# ESCON_Module_48.net
KiCad netlist of a schematic drawn in EAGLE
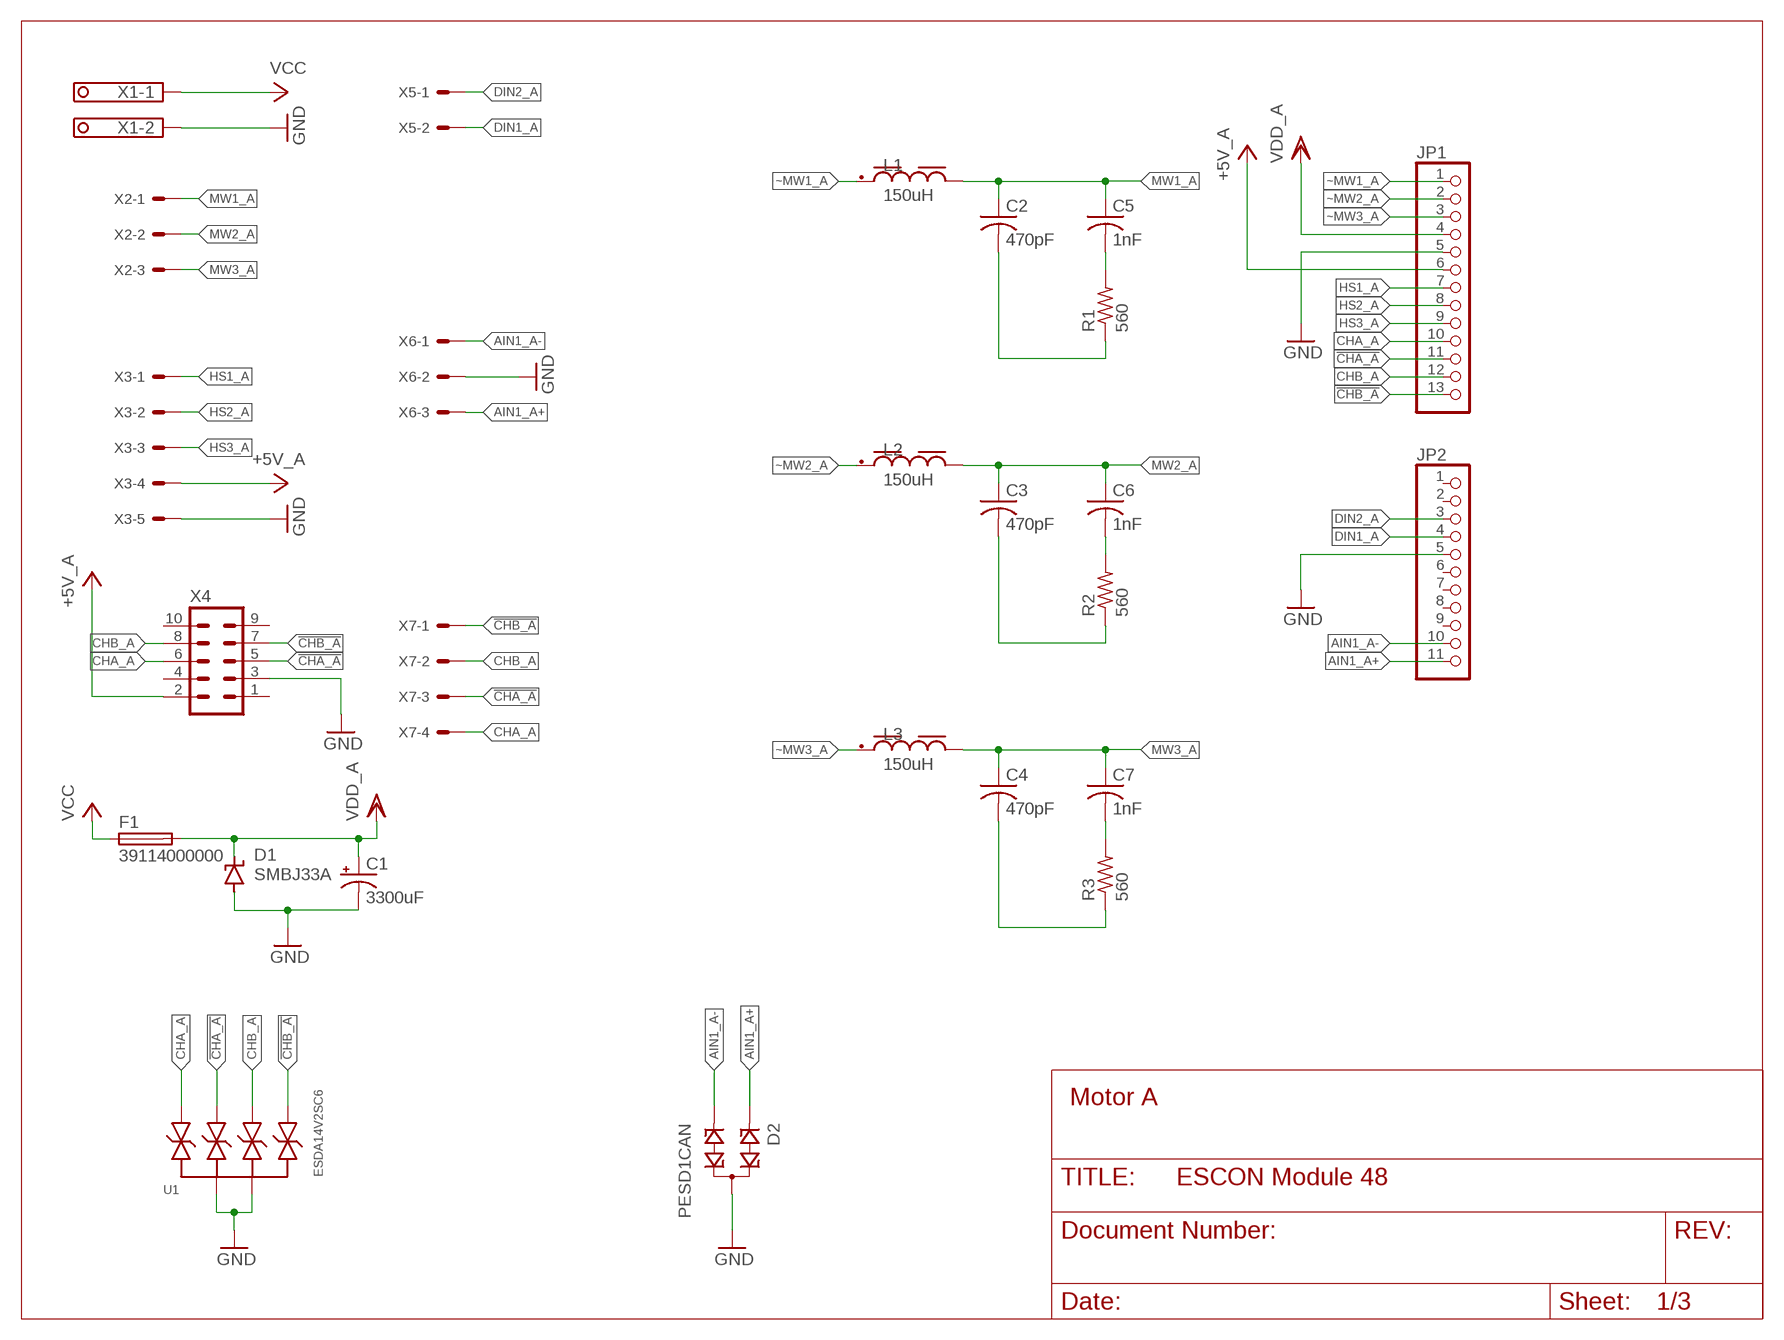
[diagram p0: schematic, sheet 1]
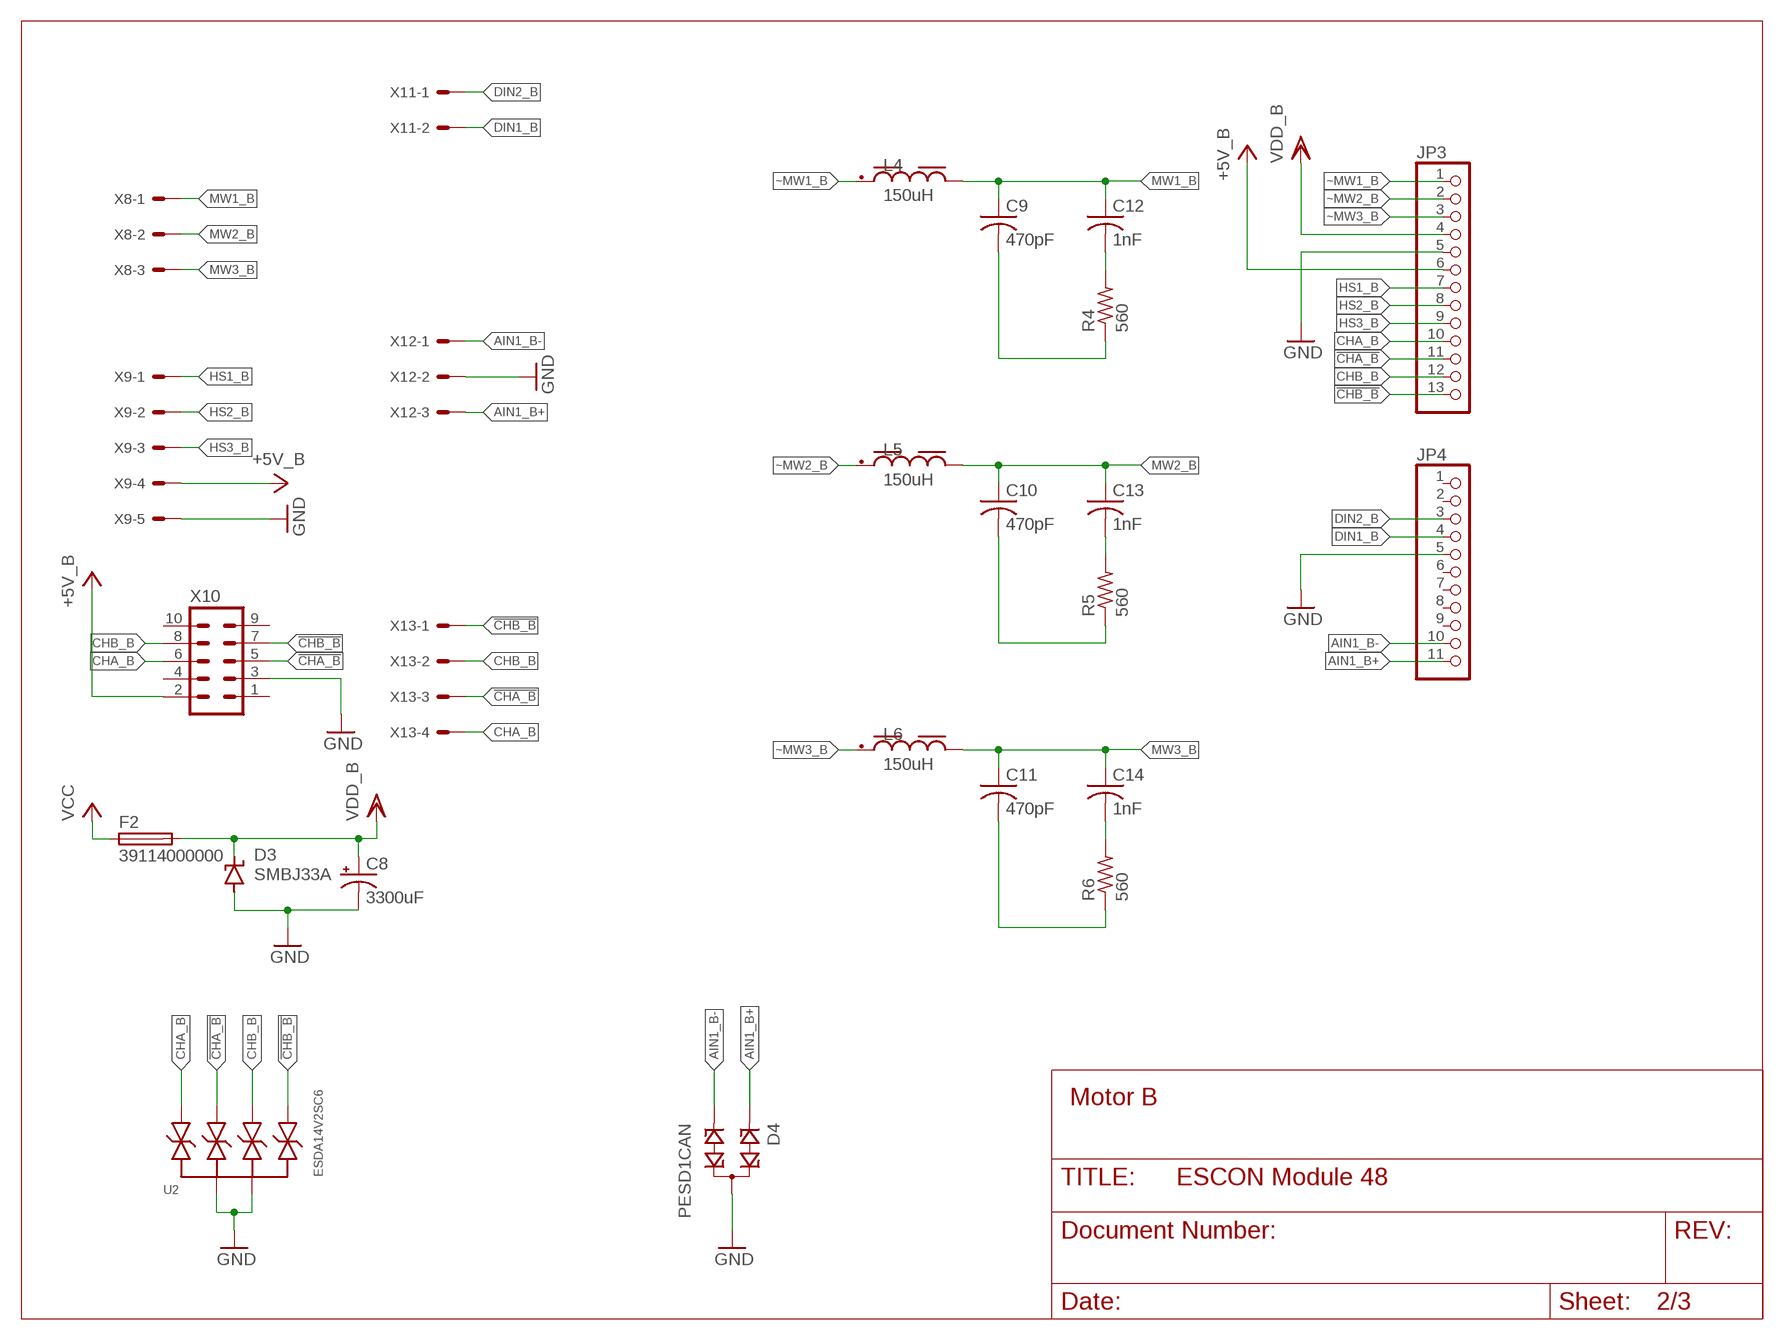
[diagram p1: schematic, sheet 2]
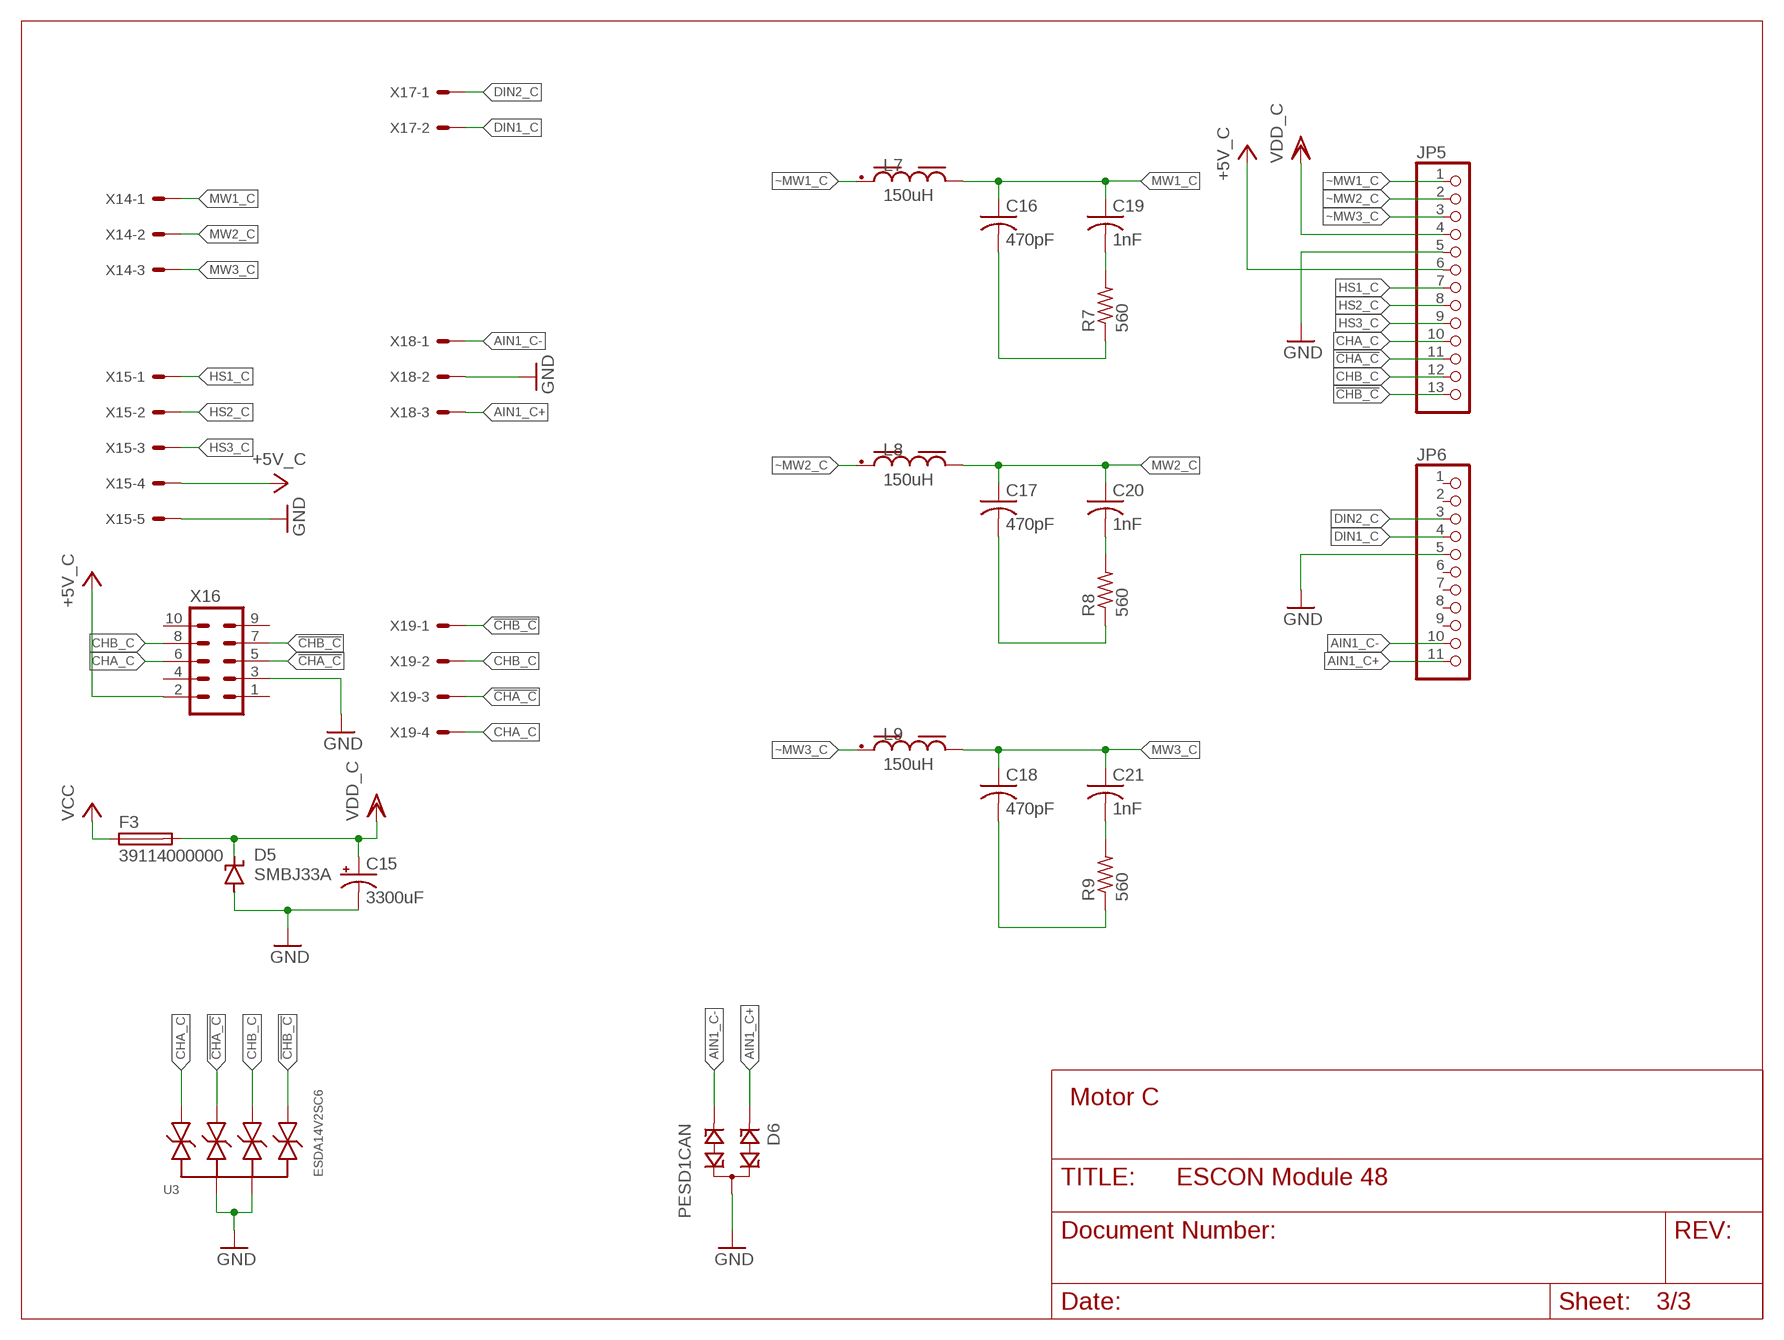
[diagram p2: schematic, sheet 3]

(export (version "E")
  (design (tool "Eeschema 10.0.6"))
  (components
    (comp (ref "C8")
      (value "3300uF")
      (footprint "eagle-import:E7,5-18")
      (libsource (lib "eagle-import") (part "CPOL-USE7.5-18"))
    )
    (comp (ref "C9")
      (value "470pF")
      (footprint "eagle-import:C0603")
      (libsource (lib "eagle-import") (part "C-USC0603"))
    )
    (comp (ref "C10")
      (value "470pF")
      (footprint "eagle-import:C0603")
      (libsource (lib "eagle-import") (part "C-USC0603"))
    )
    (comp (ref "C11")
      (value "470pF")
      (footprint "eagle-import:C0603")
      (libsource (lib "eagle-import") (part "C-USC0603"))
    )
    (comp (ref "C12")
      (value "1nF")
      (footprint "eagle-import:C0603")
      (libsource (lib "eagle-import") (part "C-USC0603"))
    )
    (comp (ref "C13")
      (value "1nF")
      (footprint "eagle-import:C0603")
      (libsource (lib "eagle-import") (part "C-USC0603"))
    )
    (comp (ref "C14")
      (value "1nF")
      (footprint "eagle-import:C0603")
      (libsource (lib "eagle-import") (part "C-USC0603"))
    )
    (comp (ref "D3")
      (value "SMBJ33A")
      (footprint "eagle-import:SMBJ")
      (libsource (lib "eagle-import") (part "SUPPRESSOR-SMBJ"))
    )
    (comp (ref "D4")
      (value "PESD1CAN")
      (footprint "eagle-import:SOT23")
      (libsource (lib "eagle-import") (part "PESD1CAN"))
    )
    (comp (ref "F2")
      (value "39114000000")
      (footprint "eagle-import:TE5")
      (libsource (lib "eagle-import") (part "TE5"))
    )
    (comp (ref "JP3")
      (value "PINHD-1X13")
      (footprint "eagle-import:1X13")
      (libsource (lib "eagle-import") (part "PINHD-1X13"))
    )
    (comp (ref "JP4")
      (value "PINHD-1X11")
      (footprint "eagle-import:1X11")
      (libsource (lib "eagle-import") (part "PINHD-1X11"))
    )
    (comp (ref "L4")
      (value "150uH")
      (footprint "eagle-import:WE-PD_1210")
      (libsource (lib "eagle-import") (part "WE-PD_1210_7447709151"))
    )
    (comp (ref "L5")
      (value "150uH")
      (footprint "eagle-import:WE-PD_1210")
      (libsource (lib "eagle-import") (part "WE-PD_1210_7447709151"))
    )
    (comp (ref "L6")
      (value "150uH")
      (footprint "eagle-import:WE-PD_1210")
      (libsource (lib "eagle-import") (part "WE-PD_1210_7447709151"))
    )
    (comp (ref "R4")
      (value "560")
      (footprint "eagle-import:R0603")
      (libsource (lib "eagle-import") (part "R-US_R0603"))
    )
    (comp (ref "R5")
      (value "560")
      (footprint "eagle-import:R0603")
      (libsource (lib "eagle-import") (part "R-US_R0603"))
    )
    (comp (ref "R6")
      (value "560")
      (footprint "eagle-import:R0603")
      (libsource (lib "eagle-import") (part "R-US_R0603"))
    )
    (comp (ref "U2")
      (value "ESDA14V2SC6")
      (footprint "eagle-import:SOT95P280X145-6N")
      (fields (field (name "MF") "STMicroelectronics"))
      (libsource (lib "eagle-import") (part "ESDA14V2SC6"))
    )
    (comp (ref "X8")
      (value "JST-XH-03-PIN-LONG-PAD")
      (footprint "eagle-import:JST-XH-03-PACKAGE-LONG-PAD")
      (libsource (lib "eagle-import") (part "JST-XH-03-PIN-LONG-PAD"))
    )
    (comp (ref "X9")
      (value "JST-XH-05-PIN-LONG-PAD")
      (footprint "eagle-import:JST-XH-05-PACKAGE-LONG-PAD")
      (libsource (lib "eagle-import") (part "JST-XH-05-PIN-LONG-PAD"))
    )
    (comp (ref "X10")
      (value "ML10LP-V")
      (footprint "eagle-import:10LP-V")
      (libsource (lib "eagle-import") (part "ML10LP-V"))
    )
    (comp (ref "X11")
      (value "JST-XH-02-PIN-LONG-PAD")
      (footprint "eagle-import:JST-XH-02-PACKAGE-LONG-PAD")
      (libsource (lib "eagle-import") (part "JST-XH-02-PIN-LONG-PAD"))
    )
    (comp (ref "X12")
      (value "JST-XH-03-PIN-LONG-PAD")
      (footprint "eagle-import:JST-XH-03-PACKAGE-LONG-PAD")
      (libsource (lib "eagle-import") (part "JST-XH-03-PIN-LONG-PAD"))
    )
    (comp (ref "X13")
      (value "JST-XH-04-PIN-LONG-PAD")
      (footprint "eagle-import:JST-XH-04-PACKAGE-LONG-PAD")
      (libsource (lib "eagle-import") (part "JST-XH-04-PIN-LONG-PAD"))
    )
    (comp (ref "C15")
      (value "3300uF")
      (footprint "eagle-import:E7,5-18")
      (libsource (lib "eagle-import") (part "CPOL-USE7.5-18"))
    )
    (comp (ref "C16")
      (value "470pF")
      (footprint "eagle-import:C0603")
      (libsource (lib "eagle-import") (part "C-USC0603"))
    )
    (comp (ref "C17")
      (value "470pF")
      (footprint "eagle-import:C0603")
      (libsource (lib "eagle-import") (part "C-USC0603"))
    )
    (comp (ref "C18")
      (value "470pF")
      (footprint "eagle-import:C0603")
      (libsource (lib "eagle-import") (part "C-USC0603"))
    )
    (comp (ref "C19")
      (value "1nF")
      (footprint "eagle-import:C0603")
      (libsource (lib "eagle-import") (part "C-USC0603"))
    )
    (comp (ref "C20")
      (value "1nF")
      (footprint "eagle-import:C0603")
      (libsource (lib "eagle-import") (part "C-USC0603"))
    )
    (comp (ref "C21")
      (value "1nF")
      (footprint "eagle-import:C0603")
      (libsource (lib "eagle-import") (part "C-USC0603"))
    )
    (comp (ref "D5")
      (value "SMBJ33A")
      (footprint "eagle-import:SMBJ")
      (libsource (lib "eagle-import") (part "SUPPRESSOR-SMBJ"))
    )
    (comp (ref "D6")
      (value "PESD1CAN")
      (footprint "eagle-import:SOT23")
      (libsource (lib "eagle-import") (part "PESD1CAN"))
    )
    (comp (ref "F3")
      (value "39114000000")
      (footprint "eagle-import:TE5")
      (libsource (lib "eagle-import") (part "TE5"))
    )
    (comp (ref "JP5")
      (value "PINHD-1X13")
      (footprint "eagle-import:1X13")
      (libsource (lib "eagle-import") (part "PINHD-1X13"))
    )
    (comp (ref "JP6")
      (value "PINHD-1X11")
      (footprint "eagle-import:1X11")
      (libsource (lib "eagle-import") (part "PINHD-1X11"))
    )
    (comp (ref "L7")
      (value "150uH")
      (footprint "eagle-import:WE-PD_1210")
      (libsource (lib "eagle-import") (part "WE-PD_1210_7447709151"))
    )
    (comp (ref "L8")
      (value "150uH")
      (footprint "eagle-import:WE-PD_1210")
      (libsource (lib "eagle-import") (part "WE-PD_1210_7447709151"))
    )
    (comp (ref "L9")
      (value "150uH")
      (footprint "eagle-import:WE-PD_1210")
      (libsource (lib "eagle-import") (part "WE-PD_1210_7447709151"))
    )
    (comp (ref "R7")
      (value "560")
      (footprint "eagle-import:R0603")
      (libsource (lib "eagle-import") (part "R-US_R0603"))
    )
    (comp (ref "R8")
      (value "560")
      (footprint "eagle-import:R0603")
      (libsource (lib "eagle-import") (part "R-US_R0603"))
    )
    (comp (ref "R9")
      (value "560")
      (footprint "eagle-import:R0603")
      (libsource (lib "eagle-import") (part "R-US_R0603"))
    )
    (comp (ref "U3")
      (value "ESDA14V2SC6")
      (footprint "eagle-import:SOT95P280X145-6N")
      (fields (field (name "MF") "STMicroelectronics"))
      (libsource (lib "eagle-import") (part "ESDA14V2SC6"))
    )
    (comp (ref "X14")
      (value "JST-XH-03-PIN-LONG-PAD")
      (footprint "eagle-import:JST-XH-03-PACKAGE-LONG-PAD")
      (libsource (lib "eagle-import") (part "JST-XH-03-PIN-LONG-PAD"))
    )
    (comp (ref "X15")
      (value "JST-XH-05-PIN-LONG-PAD")
      (footprint "eagle-import:JST-XH-05-PACKAGE-LONG-PAD")
      (libsource (lib "eagle-import") (part "JST-XH-05-PIN-LONG-PAD"))
    )
    (comp (ref "X16")
      (value "ML10LP-V")
      (footprint "eagle-import:10LP-V")
      (libsource (lib "eagle-import") (part "ML10LP-V"))
    )
    (comp (ref "X17")
      (value "JST-XH-02-PIN-LONG-PAD")
      (footprint "eagle-import:JST-XH-02-PACKAGE-LONG-PAD")
      (libsource (lib "eagle-import") (part "JST-XH-02-PIN-LONG-PAD"))
    )
    (comp (ref "X18")
      (value "JST-XH-03-PIN-LONG-PAD")
      (footprint "eagle-import:JST-XH-03-PACKAGE-LONG-PAD")
      (libsource (lib "eagle-import") (part "JST-XH-03-PIN-LONG-PAD"))
    )
    (comp (ref "X19")
      (value "JST-XH-04-PIN-LONG-PAD")
      (footprint "eagle-import:JST-XH-04-PACKAGE-LONG-PAD")
      (libsource (lib "eagle-import") (part "JST-XH-04-PIN-LONG-PAD"))
    )
    (comp (ref "C1")
      (value "3300uF")
      (footprint "eagle-import:E7,5-18")
      (libsource (lib "eagle-import") (part "CPOL-USE7.5-18"))
    )
    (comp (ref "C2")
      (value "470pF")
      (footprint "eagle-import:C0603")
      (libsource (lib "eagle-import") (part "C-USC0603"))
    )
    (comp (ref "C3")
      (value "470pF")
      (footprint "eagle-import:C0603")
      (libsource (lib "eagle-import") (part "C-USC0603"))
    )
    (comp (ref "C4")
      (value "470pF")
      (footprint "eagle-import:C0603")
      (libsource (lib "eagle-import") (part "C-USC0603"))
    )
    (comp (ref "C5")
      (value "1nF")
      (footprint "eagle-import:C0603")
      (libsource (lib "eagle-import") (part "C-USC0603"))
    )
    (comp (ref "C6")
      (value "1nF")
      (footprint "eagle-import:C0603")
      (libsource (lib "eagle-import") (part "C-USC0603"))
    )
    (comp (ref "C7")
      (value "1nF")
      (footprint "eagle-import:C0603")
      (libsource (lib "eagle-import") (part "C-USC0603"))
    )
    (comp (ref "D1")
      (value "SMBJ33A")
      (footprint "eagle-import:SMBJ")
      (libsource (lib "eagle-import") (part "SUPPRESSOR-SMBJ"))
    )
    (comp (ref "D2")
      (value "PESD1CAN")
      (footprint "eagle-import:SOT23")
      (libsource (lib "eagle-import") (part "PESD1CAN"))
    )
    (comp (ref "F1")
      (value "39114000000")
      (footprint "eagle-import:TE5")
      (libsource (lib "eagle-import") (part "TE5"))
    )
    (comp (ref "JP1")
      (value "PINHD-1X13")
      (footprint "eagle-import:1X13")
      (libsource (lib "eagle-import") (part "PINHD-1X13"))
    )
    (comp (ref "JP2")
      (value "PINHD-1X11")
      (footprint "eagle-import:1X11")
      (libsource (lib "eagle-import") (part "PINHD-1X11"))
    )
    (comp (ref "L1")
      (value "150uH")
      (footprint "eagle-import:WE-PD_1210")
      (libsource (lib "eagle-import") (part "WE-PD_1210_7447709151"))
    )
    (comp (ref "L2")
      (value "150uH")
      (footprint "eagle-import:WE-PD_1210")
      (libsource (lib "eagle-import") (part "WE-PD_1210_7447709151"))
    )
    (comp (ref "L3")
      (value "150uH")
      (footprint "eagle-import:WE-PD_1210")
      (libsource (lib "eagle-import") (part "WE-PD_1210_7447709151"))
    )
    (comp (ref "R1")
      (value "560")
      (footprint "eagle-import:R0603")
      (libsource (lib "eagle-import") (part "R-US_R0603"))
    )
    (comp (ref "R2")
      (value "560")
      (footprint "eagle-import:R0603")
      (libsource (lib "eagle-import") (part "R-US_R0603"))
    )
    (comp (ref "R3")
      (value "560")
      (footprint "eagle-import:R0603")
      (libsource (lib "eagle-import") (part "R-US_R0603"))
    )
    (comp (ref "U1")
      (value "ESDA14V2SC6")
      (footprint "eagle-import:SOT95P280X145-6N")
      (fields (field (name "MF") "STMicroelectronics"))
      (libsource (lib "eagle-import") (part "ESDA14V2SC6"))
    )
    (comp (ref "X1")
      (value "TERMINAL-BLOCK-3.5MM-2-PIN-LONG-PAD")
      (footprint "eagle-import:TERMINAL-BLOCK-2-PIN-3.5MM-LONG-PAD")
      (libsource (lib "eagle-import") (part "TERMINAL-BLOCK-3.5MM-2-PIN-LONG-PAD"))
    )
    (comp (ref "X2")
      (value "JST-XH-03-PIN-LONG-PAD")
      (footprint "eagle-import:JST-XH-03-PACKAGE-LONG-PAD")
      (libsource (lib "eagle-import") (part "JST-XH-03-PIN-LONG-PAD"))
    )
    (comp (ref "X3")
      (value "JST-XH-05-PIN-LONG-PAD")
      (footprint "eagle-import:JST-XH-05-PACKAGE-LONG-PAD")
      (libsource (lib "eagle-import") (part "JST-XH-05-PIN-LONG-PAD"))
    )
    (comp (ref "X4")
      (value "ML10LP-V")
      (footprint "eagle-import:10LP-V")
      (libsource (lib "eagle-import") (part "ML10LP-V"))
    )
    (comp (ref "X5")
      (value "JST-XH-02-PIN-LONG-PAD")
      (footprint "eagle-import:JST-XH-02-PACKAGE-LONG-PAD")
      (libsource (lib "eagle-import") (part "JST-XH-02-PIN-LONG-PAD"))
    )
    (comp (ref "X6")
      (value "JST-XH-03-PIN-LONG-PAD")
      (footprint "eagle-import:JST-XH-03-PACKAGE-LONG-PAD")
      (libsource (lib "eagle-import") (part "JST-XH-03-PIN-LONG-PAD"))
    )
    (comp (ref "X7")
      (value "JST-XH-04-PIN-LONG-PAD")
      (footprint "eagle-import:JST-XH-04-PACKAGE-LONG-PAD")
      (libsource (lib "eagle-import") (part "JST-XH-04-PIN-LONG-PAD"))
    )
  )
  (nets
    (net (code "1") (name "+5V_A") (class "Default")
      (node (ref "JP1") (pin "6") (pinfunction "6_6") (pintype "passive"))
      (node (ref "X3") (pin "4") (pinfunction "S_4") (pintype "passive"))
      (node (ref "X4") (pin "2") (pinfunction "2_2") (pintype "bidirectional"))
    )
    (net (code "2") (name "+5V_B") (class "Default")
      (node (ref "JP3") (pin "6") (pinfunction "6_6") (pintype "passive"))
      (node (ref "X10") (pin "2") (pinfunction "2_2") (pintype "bidirectional"))
      (node (ref "X9") (pin "4") (pinfunction "S_4") (pintype "passive"))
    )
    (net (code "3") (name "+5V_C") (class "Default")
      (node (ref "JP5") (pin "6") (pinfunction "6_6") (pintype "passive"))
      (node (ref "X15") (pin "4") (pinfunction "S_4") (pintype "passive"))
      (node (ref "X16") (pin "2") (pinfunction "2_2") (pintype "bidirectional"))
    )
    (net (code "4") (name "AIN1_A+") (class "Default")
      (node (ref "D2") (pin "1") (pinfunction "1_1") (pintype "passive"))
      (node (ref "JP2") (pin "11") (pinfunction "11_11") (pintype "passive"))
      (node (ref "X6") (pin "3") (pinfunction "S_3") (pintype "passive"))
    )
    (net (code "5") (name "AIN1_A-") (class "Default")
      (node (ref "D2") (pin "2") (pinfunction "2_2") (pintype "passive"))
      (node (ref "JP2") (pin "10") (pinfunction "10_10") (pintype "passive"))
      (node (ref "X6") (pin "1") (pinfunction "S_1") (pintype "passive"))
    )
    (net (code "6") (name "AIN1_B+") (class "Default")
      (node (ref "D4") (pin "1") (pinfunction "1_1") (pintype "passive"))
      (node (ref "JP4") (pin "11") (pinfunction "11_11") (pintype "passive"))
      (node (ref "X12") (pin "3") (pinfunction "S_3") (pintype "passive"))
    )
    (net (code "7") (name "AIN1_B-") (class "Default")
      (node (ref "D4") (pin "2") (pinfunction "2_2") (pintype "passive"))
      (node (ref "JP4") (pin "10") (pinfunction "10_10") (pintype "passive"))
      (node (ref "X12") (pin "1") (pinfunction "S_1") (pintype "passive"))
    )
    (net (code "8") (name "AIN1_C+") (class "Default")
      (node (ref "D6") (pin "1") (pinfunction "1_1") (pintype "passive"))
      (node (ref "JP6") (pin "11") (pinfunction "11_11") (pintype "passive"))
      (node (ref "X18") (pin "3") (pinfunction "S_3") (pintype "passive"))
    )
    (net (code "9") (name "AIN1_C-") (class "Default")
      (node (ref "D6") (pin "2") (pinfunction "2_2") (pintype "passive"))
      (node (ref "JP6") (pin "10") (pinfunction "10_10") (pintype "passive"))
      (node (ref "X18") (pin "1") (pinfunction "S_1") (pintype "passive"))
    )
    (net (code "10") (name "CHA_A") (class "Default")
      (node (ref "JP1") (pin "10") (pinfunction "10_10") (pintype "passive"))
      (node (ref "U1") (pin "1") (pinfunction "1_1") (pintype "passive"))
      (node (ref "X4") (pin "6") (pinfunction "6_6") (pintype "bidirectional"))
      (node (ref "X7") (pin "4") (pinfunction "S_4") (pintype "passive"))
    )
    (net (code "11") (name "CHA_B") (class "Default")
      (node (ref "JP3") (pin "10") (pinfunction "10_10") (pintype "passive"))
      (node (ref "U2") (pin "1") (pinfunction "1_1") (pintype "passive"))
      (node (ref "X10") (pin "6") (pinfunction "6_6") (pintype "bidirectional"))
      (node (ref "X13") (pin "4") (pinfunction "S_4") (pintype "passive"))
    )
    (net (code "12") (name "CHA_C") (class "Default")
      (node (ref "JP5") (pin "10") (pinfunction "10_10") (pintype "passive"))
      (node (ref "U3") (pin "1") (pinfunction "1_1") (pintype "passive"))
      (node (ref "X16") (pin "6") (pinfunction "6_6") (pintype "bidirectional"))
      (node (ref "X19") (pin "4") (pinfunction "S_4") (pintype "passive"))
    )
    (net (code "13") (name "CHB_A") (class "Default")
      (node (ref "JP1") (pin "12") (pinfunction "12_12") (pintype "passive"))
      (node (ref "U1") (pin "4") (pinfunction "4_4") (pintype "passive"))
      (node (ref "X4") (pin "8") (pinfunction "8_8") (pintype "bidirectional"))
      (node (ref "X7") (pin "2") (pinfunction "S_2") (pintype "passive"))
    )
    (net (code "14") (name "CHB_B") (class "Default")
      (node (ref "JP3") (pin "12") (pinfunction "12_12") (pintype "passive"))
      (node (ref "U2") (pin "4") (pinfunction "4_4") (pintype "passive"))
      (node (ref "X10") (pin "8") (pinfunction "8_8") (pintype "bidirectional"))
      (node (ref "X13") (pin "2") (pinfunction "S_2") (pintype "passive"))
    )
    (net (code "15") (name "CHB_C") (class "Default")
      (node (ref "JP5") (pin "12") (pinfunction "12_12") (pintype "passive"))
      (node (ref "U3") (pin "4") (pinfunction "4_4") (pintype "passive"))
      (node (ref "X16") (pin "8") (pinfunction "8_8") (pintype "bidirectional"))
      (node (ref "X19") (pin "2") (pinfunction "S_2") (pintype "passive"))
    )
    (net (code "16") (name "DIN1_A") (class "Default")
      (node (ref "JP2") (pin "4") (pinfunction "4_4") (pintype "passive"))
      (node (ref "X5") (pin "2") (pinfunction "S_2") (pintype "passive"))
    )
    (net (code "17") (name "DIN1_B") (class "Default")
      (node (ref "JP4") (pin "4") (pinfunction "4_4") (pintype "passive"))
      (node (ref "X11") (pin "2") (pinfunction "S_2") (pintype "passive"))
    )
    (net (code "18") (name "DIN1_C") (class "Default")
      (node (ref "JP6") (pin "4") (pinfunction "4_4") (pintype "passive"))
      (node (ref "X17") (pin "2") (pinfunction "S_2") (pintype "passive"))
    )
    (net (code "19") (name "DIN2_A") (class "Default")
      (node (ref "JP2") (pin "3") (pinfunction "3_3") (pintype "passive"))
      (node (ref "X5") (pin "1") (pinfunction "S_1") (pintype "passive"))
    )
    (net (code "20") (name "DIN2_B") (class "Default")
      (node (ref "JP4") (pin "3") (pinfunction "3_3") (pintype "passive"))
      (node (ref "X11") (pin "1") (pinfunction "S_1") (pintype "passive"))
    )
    (net (code "21") (name "DIN2_C") (class "Default")
      (node (ref "JP6") (pin "3") (pinfunction "3_3") (pintype "passive"))
      (node (ref "X17") (pin "1") (pinfunction "S_1") (pintype "passive"))
    )
    (net (code "22") (name "GND") (class "Default")
      (node (ref "C1") (pin "-") (pinfunction "-_-") (pintype "passive"))
      (node (ref "C15") (pin "-") (pinfunction "-_-") (pintype "passive"))
      (node (ref "C8") (pin "-") (pinfunction "-_-") (pintype "passive"))
      (node (ref "D1") (pin "A") (pinfunction "A_A") (pintype "passive"))
      (node (ref "D2") (pin "3") (pinfunction "3_3") (pintype "passive"))
      (node (ref "D3") (pin "A") (pinfunction "A_A") (pintype "passive"))
      (node (ref "D4") (pin "3") (pinfunction "3_3") (pintype "passive"))
      (node (ref "D5") (pin "A") (pinfunction "A_A") (pintype "passive"))
      (node (ref "D6") (pin "3") (pinfunction "3_3") (pintype "passive"))
      (node (ref "JP1") (pin "5") (pinfunction "5_5") (pintype "passive"))
      (node (ref "JP2") (pin "5") (pinfunction "5_5") (pintype "passive"))
      (node (ref "JP3") (pin "5") (pinfunction "5_5") (pintype "passive"))
      (node (ref "JP4") (pin "5") (pinfunction "5_5") (pintype "passive"))
      (node (ref "JP5") (pin "5") (pinfunction "5_5") (pintype "passive"))
      (node (ref "JP6") (pin "5") (pinfunction "5_5") (pintype "passive"))
      (node (ref "U1") (pin "2") (pinfunction "2_2") (pintype "passive"))
      (node (ref "U1") (pin "5") (pinfunction "5_5") (pintype "passive"))
      (node (ref "U2") (pin "2") (pinfunction "2_2") (pintype "passive"))
      (node (ref "U2") (pin "5") (pinfunction "5_5") (pintype "passive"))
      (node (ref "U3") (pin "2") (pinfunction "2_2") (pintype "passive"))
      (node (ref "U3") (pin "5") (pinfunction "5_5") (pintype "passive"))
      (node (ref "X1") (pin "2") (pinfunction "K_2") (pintype "passive"))
      (node (ref "X10") (pin "3") (pinfunction "3_3") (pintype "bidirectional"))
      (node (ref "X12") (pin "2") (pinfunction "S_2") (pintype "passive"))
      (node (ref "X15") (pin "5") (pinfunction "S_5") (pintype "passive"))
      (node (ref "X16") (pin "3") (pinfunction "3_3") (pintype "bidirectional"))
      (node (ref "X18") (pin "2") (pinfunction "S_2") (pintype "passive"))
      (node (ref "X3") (pin "5") (pinfunction "S_5") (pintype "passive"))
      (node (ref "X4") (pin "3") (pinfunction "3_3") (pintype "bidirectional"))
      (node (ref "X6") (pin "2") (pinfunction "S_2") (pintype "passive"))
      (node (ref "X9") (pin "5") (pinfunction "S_5") (pintype "passive"))
    )
    (net (code "23") (name "HS1_A") (class "Default")
      (node (ref "JP1") (pin "7") (pinfunction "7_7") (pintype "passive"))
      (node (ref "X3") (pin "1") (pinfunction "S_1") (pintype "passive"))
    )
    (net (code "24") (name "HS1_B") (class "Default")
      (node (ref "JP3") (pin "7") (pinfunction "7_7") (pintype "passive"))
      (node (ref "X9") (pin "1") (pinfunction "S_1") (pintype "passive"))
    )
    (net (code "25") (name "HS1_C") (class "Default")
      (node (ref "JP5") (pin "7") (pinfunction "7_7") (pintype "passive"))
      (node (ref "X15") (pin "1") (pinfunction "S_1") (pintype "passive"))
    )
    (net (code "26") (name "HS2_A") (class "Default")
      (node (ref "JP1") (pin "8") (pinfunction "8_8") (pintype "passive"))
      (node (ref "X3") (pin "2") (pinfunction "S_2") (pintype "passive"))
    )
    (net (code "27") (name "HS2_B") (class "Default")
      (node (ref "JP3") (pin "8") (pinfunction "8_8") (pintype "passive"))
      (node (ref "X9") (pin "2") (pinfunction "S_2") (pintype "passive"))
    )
    (net (code "28") (name "HS2_C") (class "Default")
      (node (ref "JP5") (pin "8") (pinfunction "8_8") (pintype "passive"))
      (node (ref "X15") (pin "2") (pinfunction "S_2") (pintype "passive"))
    )
    (net (code "29") (name "HS3_A") (class "Default")
      (node (ref "JP1") (pin "9") (pinfunction "9_9") (pintype "passive"))
      (node (ref "X3") (pin "3") (pinfunction "S_3") (pintype "passive"))
    )
    (net (code "30") (name "HS3_B") (class "Default")
      (node (ref "JP3") (pin "9") (pinfunction "9_9") (pintype "passive"))
      (node (ref "X9") (pin "3") (pinfunction "S_3") (pintype "passive"))
    )
    (net (code "31") (name "HS3_C") (class "Default")
      (node (ref "JP5") (pin "9") (pinfunction "9_9") (pintype "passive"))
      (node (ref "X15") (pin "3") (pinfunction "S_3") (pintype "passive"))
    )
    (net (code "32") (name "MW1_A") (class "Default")
      (node (ref "C2") (pin "1") (pinfunction "1_1") (pintype "passive"))
      (node (ref "C5") (pin "1") (pinfunction "1_1") (pintype "passive"))
      (node (ref "L1") (pin "2") (pinfunction "2_2") (pintype "passive"))
      (node (ref "X2") (pin "1") (pinfunction "S_1") (pintype "passive"))
    )
    (net (code "33") (name "MW1_B") (class "Default")
      (node (ref "C12") (pin "1") (pinfunction "1_1") (pintype "passive"))
      (node (ref "C9") (pin "1") (pinfunction "1_1") (pintype "passive"))
      (node (ref "L4") (pin "2") (pinfunction "2_2") (pintype "passive"))
      (node (ref "X8") (pin "1") (pinfunction "S_1") (pintype "passive"))
    )
    (net (code "34") (name "MW1_C") (class "Default")
      (node (ref "C16") (pin "1") (pinfunction "1_1") (pintype "passive"))
      (node (ref "C19") (pin "1") (pinfunction "1_1") (pintype "passive"))
      (node (ref "L7") (pin "2") (pinfunction "2_2") (pintype "passive"))
      (node (ref "X14") (pin "1") (pinfunction "S_1") (pintype "passive"))
    )
    (net (code "35") (name "MW2_A") (class "Default")
      (node (ref "C3") (pin "1") (pinfunction "1_1") (pintype "passive"))
      (node (ref "C6") (pin "1") (pinfunction "1_1") (pintype "passive"))
      (node (ref "L2") (pin "2") (pinfunction "2_2") (pintype "passive"))
      (node (ref "X2") (pin "2") (pinfunction "S_2") (pintype "passive"))
    )
    (net (code "36") (name "MW2_B") (class "Default")
      (node (ref "C10") (pin "1") (pinfunction "1_1") (pintype "passive"))
      (node (ref "C13") (pin "1") (pinfunction "1_1") (pintype "passive"))
      (node (ref "L5") (pin "2") (pinfunction "2_2") (pintype "passive"))
      (node (ref "X8") (pin "2") (pinfunction "S_2") (pintype "passive"))
    )
    (net (code "37") (name "MW2_C") (class "Default")
      (node (ref "C17") (pin "1") (pinfunction "1_1") (pintype "passive"))
      (node (ref "C20") (pin "1") (pinfunction "1_1") (pintype "passive"))
      (node (ref "L8") (pin "2") (pinfunction "2_2") (pintype "passive"))
      (node (ref "X14") (pin "2") (pinfunction "S_2") (pintype "passive"))
    )
    (net (code "38") (name "MW3_A") (class "Default")
      (node (ref "C4") (pin "1") (pinfunction "1_1") (pintype "passive"))
      (node (ref "C7") (pin "1") (pinfunction "1_1") (pintype "passive"))
      (node (ref "L3") (pin "2") (pinfunction "2_2") (pintype "passive"))
      (node (ref "X2") (pin "3") (pinfunction "S_3") (pintype "passive"))
    )
    (net (code "39") (name "MW3_B") (class "Default")
      (node (ref "C11") (pin "1") (pinfunction "1_1") (pintype "passive"))
      (node (ref "C14") (pin "1") (pinfunction "1_1") (pintype "passive"))
      (node (ref "L6") (pin "2") (pinfunction "2_2") (pintype "passive"))
      (node (ref "X8") (pin "3") (pinfunction "S_3") (pintype "passive"))
    )
    (net (code "40") (name "MW3_C") (class "Default")
      (node (ref "C18") (pin "1") (pinfunction "1_1") (pintype "passive"))
      (node (ref "C21") (pin "1") (pinfunction "1_1") (pintype "passive"))
      (node (ref "L9") (pin "2") (pinfunction "2_2") (pintype "passive"))
      (node (ref "X14") (pin "3") (pinfunction "S_3") (pintype "passive"))
    )
    (net (code "41") (name "Net-(C2-Pad2)") (class "Default")
      (node (ref "C2") (pin "2") (pinfunction "2_2") (pintype "passive"))
      (node (ref "R1") (pin "1") (pinfunction "1_1") (pintype "passive"))
    )
    (net (code "42") (name "Net-(C3-Pad2)") (class "Default")
      (node (ref "C3") (pin "2") (pinfunction "2_2") (pintype "passive"))
      (node (ref "R2") (pin "1") (pinfunction "1_1") (pintype "passive"))
    )
    (net (code "43") (name "Net-(C4-Pad2)") (class "Default")
      (node (ref "C4") (pin "2") (pinfunction "2_2") (pintype "passive"))
      (node (ref "R3") (pin "1") (pinfunction "1_1") (pintype "passive"))
    )
    (net (code "44") (name "Net-(C5-Pad2)") (class "Default")
      (node (ref "C5") (pin "2") (pinfunction "2_2") (pintype "passive"))
      (node (ref "R1") (pin "2") (pinfunction "2_2") (pintype "passive"))
    )
    (net (code "45") (name "Net-(C6-Pad2)") (class "Default")
      (node (ref "C6") (pin "2") (pinfunction "2_2") (pintype "passive"))
      (node (ref "R2") (pin "2") (pinfunction "2_2") (pintype "passive"))
    )
    (net (code "46") (name "Net-(C7-Pad2)") (class "Default")
      (node (ref "C7") (pin "2") (pinfunction "2_2") (pintype "passive"))
      (node (ref "R3") (pin "2") (pinfunction "2_2") (pintype "passive"))
    )
    (net (code "47") (name "Net-(C9-Pad2)") (class "Default")
      (node (ref "C9") (pin "2") (pinfunction "2_2") (pintype "passive"))
      (node (ref "R4") (pin "1") (pinfunction "1_1") (pintype "passive"))
    )
    (net (code "48") (name "Net-(C10-Pad2)") (class "Default")
      (node (ref "C10") (pin "2") (pinfunction "2_2") (pintype "passive"))
      (node (ref "R5") (pin "1") (pinfunction "1_1") (pintype "passive"))
    )
    (net (code "49") (name "Net-(C11-Pad2)") (class "Default")
      (node (ref "C11") (pin "2") (pinfunction "2_2") (pintype "passive"))
      (node (ref "R6") (pin "1") (pinfunction "1_1") (pintype "passive"))
    )
    (net (code "50") (name "Net-(C12-Pad2)") (class "Default")
      (node (ref "C12") (pin "2") (pinfunction "2_2") (pintype "passive"))
      (node (ref "R4") (pin "2") (pinfunction "2_2") (pintype "passive"))
    )
    (net (code "51") (name "Net-(C13-Pad2)") (class "Default")
      (node (ref "C13") (pin "2") (pinfunction "2_2") (pintype "passive"))
      (node (ref "R5") (pin "2") (pinfunction "2_2") (pintype "passive"))
    )
    (net (code "52") (name "Net-(C14-Pad2)") (class "Default")
      (node (ref "C14") (pin "2") (pinfunction "2_2") (pintype "passive"))
      (node (ref "R6") (pin "2") (pinfunction "2_2") (pintype "passive"))
    )
    (net (code "53") (name "Net-(C16-Pad2)") (class "Default")
      (node (ref "C16") (pin "2") (pinfunction "2_2") (pintype "passive"))
      (node (ref "R7") (pin "1") (pinfunction "1_1") (pintype "passive"))
    )
    (net (code "54") (name "Net-(C17-Pad2)") (class "Default")
      (node (ref "C17") (pin "2") (pinfunction "2_2") (pintype "passive"))
      (node (ref "R8") (pin "1") (pinfunction "1_1") (pintype "passive"))
    )
    (net (code "55") (name "Net-(C18-Pad2)") (class "Default")
      (node (ref "C18") (pin "2") (pinfunction "2_2") (pintype "passive"))
      (node (ref "R9") (pin "1") (pinfunction "1_1") (pintype "passive"))
    )
    (net (code "56") (name "Net-(C19-Pad2)") (class "Default")
      (node (ref "C19") (pin "2") (pinfunction "2_2") (pintype "passive"))
      (node (ref "R7") (pin "2") (pinfunction "2_2") (pintype "passive"))
    )
    (net (code "57") (name "Net-(C20-Pad2)") (class "Default")
      (node (ref "C20") (pin "2") (pinfunction "2_2") (pintype "passive"))
      (node (ref "R8") (pin "2") (pinfunction "2_2") (pintype "passive"))
    )
    (net (code "58") (name "Net-(C21-Pad2)") (class "Default")
      (node (ref "C21") (pin "2") (pinfunction "2_2") (pintype "passive"))
      (node (ref "R9") (pin "2") (pinfunction "2_2") (pintype "passive"))
    )
    (net (code "59") (name "VCC") (class "Default")
      (node (ref "F1") (pin "1") (pinfunction "1_1") (pintype "passive"))
      (node (ref "F2") (pin "1") (pinfunction "1_1") (pintype "passive"))
      (node (ref "F3") (pin "1") (pinfunction "1_1") (pintype "passive"))
      (node (ref "X1") (pin "1") (pinfunction "K_1") (pintype "passive"))
    )
    (net (code "60") (name "VDD_A") (class "Default")
      (node (ref "C1") (pin "+") (pinfunction "+_+") (pintype "passive"))
      (node (ref "D1") (pin "C") (pinfunction "C_C") (pintype "passive"))
      (node (ref "F1") (pin "2") (pinfunction "2_2") (pintype "passive"))
      (node (ref "JP1") (pin "4") (pinfunction "4_4") (pintype "passive"))
    )
    (net (code "61") (name "VDD_B") (class "Default")
      (node (ref "C8") (pin "+") (pinfunction "+_+") (pintype "passive"))
      (node (ref "D3") (pin "C") (pinfunction "C_C") (pintype "passive"))
      (node (ref "F2") (pin "2") (pinfunction "2_2") (pintype "passive"))
      (node (ref "JP3") (pin "4") (pinfunction "4_4") (pintype "passive"))
    )
    (net (code "62") (name "VDD_C") (class "Default")
      (node (ref "C15") (pin "+") (pinfunction "+_+") (pintype "passive"))
      (node (ref "D5") (pin "C") (pinfunction "C_C") (pintype "passive"))
      (node (ref "F3") (pin "2") (pinfunction "2_2") (pintype "passive"))
      (node (ref "JP5") (pin "4") (pinfunction "4_4") (pintype "passive"))
    )
    (net (code "63") (name "unconnected-(JP2-Pad1)") (class "Default")
      (node (ref "JP2") (pin "1") (pinfunction "1_1") (pintype "passive"))
    )
    (net (code "64") (name "unconnected-(JP2-Pad2)") (class "Default")
      (node (ref "JP2") (pin "2") (pinfunction "2_2") (pintype "passive"))
    )
    (net (code "65") (name "unconnected-(JP2-Pad6)") (class "Default")
      (node (ref "JP2") (pin "6") (pinfunction "6_6") (pintype "passive"))
    )
    (net (code "66") (name "unconnected-(JP2-Pad7)") (class "Default")
      (node (ref "JP2") (pin "7") (pinfunction "7_7") (pintype "passive"))
    )
    (net (code "67") (name "unconnected-(JP2-Pad8)") (class "Default")
      (node (ref "JP2") (pin "8") (pinfunction "8_8") (pintype "passive"))
    )
    (net (code "68") (name "unconnected-(JP2-Pad9)") (class "Default")
      (node (ref "JP2") (pin "9") (pinfunction "9_9") (pintype "passive"))
    )
    (net (code "69") (name "unconnected-(JP4-Pad1)") (class "Default")
      (node (ref "JP4") (pin "1") (pinfunction "1_1") (pintype "passive"))
    )
    (net (code "70") (name "unconnected-(JP4-Pad2)") (class "Default")
      (node (ref "JP4") (pin "2") (pinfunction "2_2") (pintype "passive"))
    )
    (net (code "71") (name "unconnected-(JP4-Pad6)") (class "Default")
      (node (ref "JP4") (pin "6") (pinfunction "6_6") (pintype "passive"))
    )
    (net (code "72") (name "unconnected-(JP4-Pad7)") (class "Default")
      (node (ref "JP4") (pin "7") (pinfunction "7_7") (pintype "passive"))
    )
    (net (code "73") (name "unconnected-(JP4-Pad8)") (class "Default")
      (node (ref "JP4") (pin "8") (pinfunction "8_8") (pintype "passive"))
    )
    (net (code "74") (name "unconnected-(JP4-Pad9)") (class "Default")
      (node (ref "JP4") (pin "9") (pinfunction "9_9") (pintype "passive"))
    )
    (net (code "75") (name "unconnected-(JP6-Pad1)") (class "Default")
      (node (ref "JP6") (pin "1") (pinfunction "1_1") (pintype "passive"))
    )
    (net (code "76") (name "unconnected-(JP6-Pad2)") (class "Default")
      (node (ref "JP6") (pin "2") (pinfunction "2_2") (pintype "passive"))
    )
    (net (code "77") (name "unconnected-(JP6-Pad6)") (class "Default")
      (node (ref "JP6") (pin "6") (pinfunction "6_6") (pintype "passive"))
    )
    (net (code "78") (name "unconnected-(JP6-Pad7)") (class "Default")
      (node (ref "JP6") (pin "7") (pinfunction "7_7") (pintype "passive"))
    )
    (net (code "79") (name "unconnected-(JP6-Pad8)") (class "Default")
      (node (ref "JP6") (pin "8") (pinfunction "8_8") (pintype "passive"))
    )
    (net (code "80") (name "unconnected-(JP6-Pad9)") (class "Default")
      (node (ref "JP6") (pin "9") (pinfunction "9_9") (pintype "passive"))
    )
    (net (code "81") (name "unconnected-(X4-Pad1)") (class "Default")
      (node (ref "X4") (pin "1") (pinfunction "1_1") (pintype "bidirectional"))
    )
    (net (code "82") (name "unconnected-(X4-Pad4)") (class "Default")
      (node (ref "X4") (pin "4") (pinfunction "4_4") (pintype "bidirectional"))
    )
    (net (code "83") (name "unconnected-(X4-Pad9)") (class "Default")
      (node (ref "X4") (pin "9") (pinfunction "9_9") (pintype "bidirectional"))
    )
    (net (code "84") (name "unconnected-(X4-Pad10)") (class "Default")
      (node (ref "X4") (pin "10") (pinfunction "10_10") (pintype "bidirectional"))
    )
    (net (code "85") (name "unconnected-(X10-Pad1)") (class "Default")
      (node (ref "X10") (pin "1") (pinfunction "1_1") (pintype "bidirectional"))
    )
    (net (code "86") (name "unconnected-(X10-Pad4)") (class "Default")
      (node (ref "X10") (pin "4") (pinfunction "4_4") (pintype "bidirectional"))
    )
    (net (code "87") (name "unconnected-(X10-Pad9)") (class "Default")
      (node (ref "X10") (pin "9") (pinfunction "9_9") (pintype "bidirectional"))
    )
    (net (code "88") (name "unconnected-(X10-Pad10)") (class "Default")
      (node (ref "X10") (pin "10") (pinfunction "10_10") (pintype "bidirectional"))
    )
    (net (code "89") (name "unconnected-(X16-Pad1)") (class "Default")
      (node (ref "X16") (pin "1") (pinfunction "1_1") (pintype "bidirectional"))
    )
    (net (code "90") (name "unconnected-(X16-Pad4)") (class "Default")
      (node (ref "X16") (pin "4") (pinfunction "4_4") (pintype "bidirectional"))
    )
    (net (code "91") (name "unconnected-(X16-Pad9)") (class "Default")
      (node (ref "X16") (pin "9") (pinfunction "9_9") (pintype "bidirectional"))
    )
    (net (code "92") (name "unconnected-(X16-Pad10)") (class "Default")
      (node (ref "X16") (pin "10") (pinfunction "10_10") (pintype "bidirectional"))
    )
    (net (code "93") (name "~{CHA_A}") (class "Default")
      (node (ref "JP1") (pin "11") (pinfunction "11_11") (pintype "passive"))
      (node (ref "U1") (pin "3") (pinfunction "3_3") (pintype "passive"))
      (node (ref "X4") (pin "5") (pinfunction "5_5") (pintype "bidirectional"))
      (node (ref "X7") (pin "3") (pinfunction "S_3") (pintype "passive"))
    )
    (net (code "94") (name "~{CHA_B}") (class "Default")
      (node (ref "JP3") (pin "11") (pinfunction "11_11") (pintype "passive"))
      (node (ref "U2") (pin "3") (pinfunction "3_3") (pintype "passive"))
      (node (ref "X10") (pin "5") (pinfunction "5_5") (pintype "bidirectional"))
      (node (ref "X13") (pin "3") (pinfunction "S_3") (pintype "passive"))
    )
    (net (code "95") (name "~{CHA_C}") (class "Default")
      (node (ref "JP5") (pin "11") (pinfunction "11_11") (pintype "passive"))
      (node (ref "U3") (pin "3") (pinfunction "3_3") (pintype "passive"))
      (node (ref "X16") (pin "5") (pinfunction "5_5") (pintype "bidirectional"))
      (node (ref "X19") (pin "3") (pinfunction "S_3") (pintype "passive"))
    )
    (net (code "96") (name "~{CHB_A}") (class "Default")
      (node (ref "JP1") (pin "13") (pinfunction "13_13") (pintype "passive"))
      (node (ref "U1") (pin "6") (pinfunction "6_6") (pintype "passive"))
      (node (ref "X4") (pin "7") (pinfunction "7_7") (pintype "bidirectional"))
      (node (ref "X7") (pin "1") (pinfunction "S_1") (pintype "passive"))
    )
    (net (code "97") (name "~{CHB_B}") (class "Default")
      (node (ref "JP3") (pin "13") (pinfunction "13_13") (pintype "passive"))
      (node (ref "U2") (pin "6") (pinfunction "6_6") (pintype "passive"))
      (node (ref "X10") (pin "7") (pinfunction "7_7") (pintype "bidirectional"))
      (node (ref "X13") (pin "1") (pinfunction "S_1") (pintype "passive"))
    )
    (net (code "98") (name "~{CHB_C}") (class "Default")
      (node (ref "JP5") (pin "13") (pinfunction "13_13") (pintype "passive"))
      (node (ref "U3") (pin "6") (pinfunction "6_6") (pintype "passive"))
      (node (ref "X16") (pin "7") (pinfunction "7_7") (pintype "bidirectional"))
      (node (ref "X19") (pin "1") (pinfunction "S_1") (pintype "passive"))
    )
    (net (code "99") (name "~{MW1_A}") (class "Default")
      (node (ref "JP1") (pin "1") (pinfunction "1_1") (pintype "passive"))
      (node (ref "L1") (pin "1") (pinfunction "1_1") (pintype "passive"))
    )
    (net (code "100") (name "~{MW1_B}") (class "Default")
      (node (ref "JP3") (pin "1") (pinfunction "1_1") (pintype "passive"))
      (node (ref "L4") (pin "1") (pinfunction "1_1") (pintype "passive"))
    )
    (net (code "101") (name "~{MW1_C}") (class "Default")
      (node (ref "JP5") (pin "1") (pinfunction "1_1") (pintype "passive"))
      (node (ref "L7") (pin "1") (pinfunction "1_1") (pintype "passive"))
    )
    (net (code "102") (name "~{MW2_A}") (class "Default")
      (node (ref "JP1") (pin "2") (pinfunction "2_2") (pintype "passive"))
      (node (ref "L2") (pin "1") (pinfunction "1_1") (pintype "passive"))
    )
    (net (code "103") (name "~{MW2_B}") (class "Default")
      (node (ref "JP3") (pin "2") (pinfunction "2_2") (pintype "passive"))
      (node (ref "L5") (pin "1") (pinfunction "1_1") (pintype "passive"))
    )
    (net (code "104") (name "~{MW2_C}") (class "Default")
      (node (ref "JP5") (pin "2") (pinfunction "2_2") (pintype "passive"))
      (node (ref "L8") (pin "1") (pinfunction "1_1") (pintype "passive"))
    )
    (net (code "105") (name "~{MW3_A}") (class "Default")
      (node (ref "JP1") (pin "3") (pinfunction "3_3") (pintype "passive"))
      (node (ref "L3") (pin "1") (pinfunction "1_1") (pintype "passive"))
    )
    (net (code "106") (name "~{MW3_B}") (class "Default")
      (node (ref "JP3") (pin "3") (pinfunction "3_3") (pintype "passive"))
      (node (ref "L6") (pin "1") (pinfunction "1_1") (pintype "passive"))
    )
    (net (code "107") (name "~{MW3_C}") (class "Default")
      (node (ref "JP5") (pin "3") (pinfunction "3_3") (pintype "passive"))
      (node (ref "L9") (pin "1") (pinfunction "1_1") (pintype "passive"))
    )
  )
)
